# fireguard_v1.net
KiCad netlist of a schematic drawn in EasyEDA
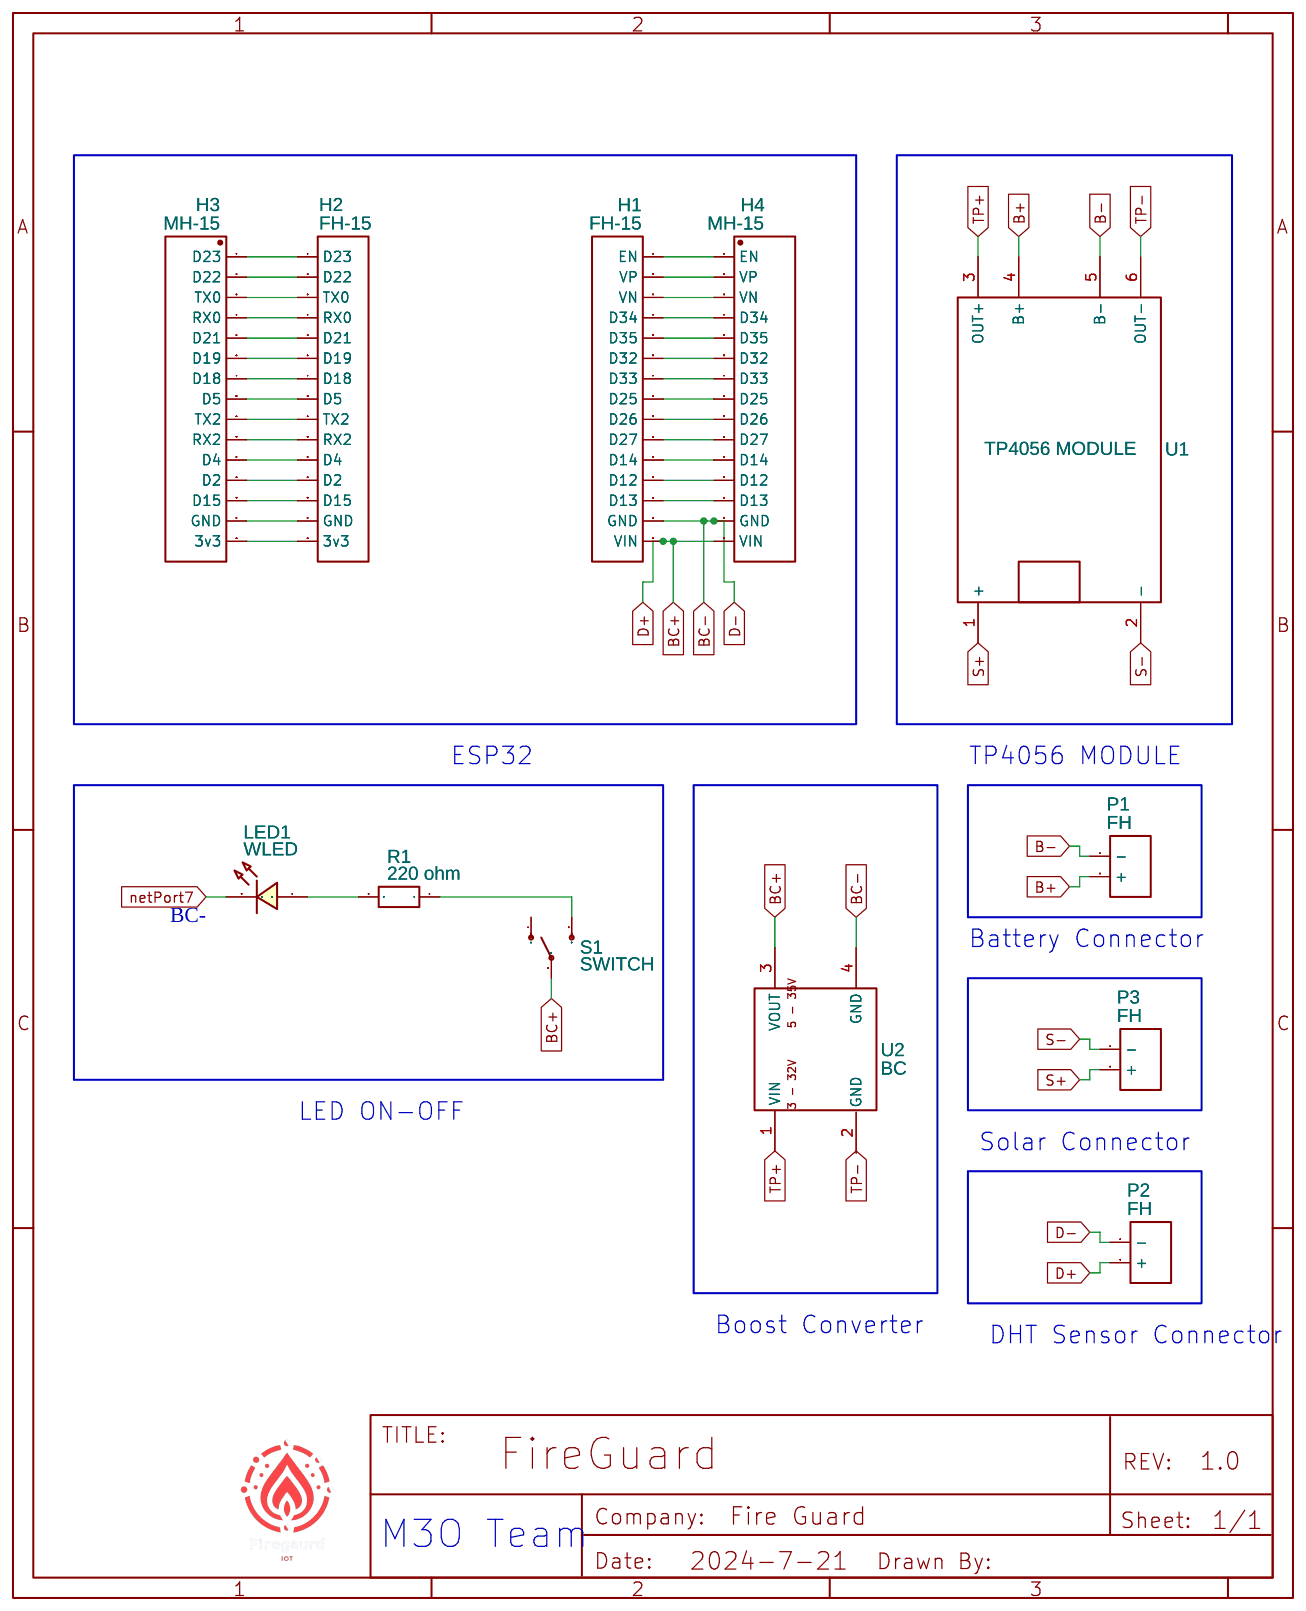
[diagram p0: schematic sheet]

(export (version "E")
  (design (tool "Eeschema 10.0.6"))
  (components
    (comp (ref "H1")
      (value "FH-15")
      (fields (field (name "Manufacturer Part") "B-2200S15P-A120") (field (name "Manufacturer") "Ckmtw(灿科盟)"))
      (libsource (lib "") (part "Header-Female-2.54_1x15_1"))
    )
    (comp (ref "H2")
      (value "FH-15")
      (fields (field (name "Manufacturer Part") "B-2200S15P-A120") (field (name "Manufacturer") "Ckmtw(灿科盟)"))
      (libsource (lib "") (part "Header-Female-2.54_1x15"))
    )
    (comp (ref "H3")
      (value "MH-15")
      (fields (field (name "Manufacturer Part") "B-2100S15P-A110") (field (name "Manufacturer") "Ckmtw(灿科盟)"))
      (libsource (lib "") (part "Header-Male-2.54_1x15_1"))
    )
    (comp (ref "H4")
      (value "MH-15")
      (fields (field (name "Manufacturer Part") "B-2100S15P-A110") (field (name "Manufacturer") "Ckmtw(灿科盟)"))
      (libsource (lib "") (part "Header-Male-2.54_1x15"))
    )
    (comp (ref "LED1") (value "WLED") (libsource (lib "") (part "LED-TH-5mm_B")))
    (comp (ref "P1")
      (value "FH")
      (fields (field (name "Manufacturer Part") "2.54-1*2P母") (field (name "Manufacturer") "BOOMELE(博穆精密)"))
      (libsource (lib "") (part "Header-Female-2.54_1x2"))
    )
    (comp (ref "P2")
      (value "FH")
      (fields (field (name "Manufacturer Part") "2.54-1*2P母") (field (name "Manufacturer") "BOOMELE(博穆精密)"))
      (libsource (lib "") (part "Header-Female-2.54_1x2"))
    )
    (comp (ref "P3")
      (value "FH")
      (fields (field (name "Manufacturer Part") "2.54-1*2P母") (field (name "Manufacturer") "BOOMELE(博穆精密)"))
      (libsource (lib "") (part "Header-Female-2.54_1x2"))
    )
    (comp (ref "R1")
      (value "220 ohm")
      (fields
        (field (name "Manufacturer Part") "Resistor_THT:R_Axial_DIN0309_L9.0mm_D3.2mm_P2.54mm_Vertical")
      )
      (libsource (lib "") (part "RESISTOR_THT{colon}R_AXIAL_DIN0309_L9.0MM_D3.2MM_P2.54MM_VERTICAL"))
    )
    (comp (ref "S1") (value "SWITCH") (libsource (lib "") (part "SWITCH-SPDT-8.5mm")))
    (comp (ref "U1") (value "TP4056 MODULE") (libsource (lib "") (part "TP4056 MODULE")))
    (comp (ref "U2") (value "BC") (libsource (lib "") (part "STEP-UP XL6009E1")))
  )
  (nets
    (net (code "1") (name "B+") (class "Default")
      (node (ref "P1") (pin "2") (pinfunction "+_2") (pintype "input"))
      (node (ref "U1") (pin "4") (pinfunction "B+_4") (pintype "unspecified"))
    )
    (net (code "2") (name "B-") (class "Default")
      (node (ref "P1") (pin "1") (pinfunction "-_1") (pintype "input"))
      (node (ref "U1") (pin "5") (pinfunction "B-_5") (pintype "unspecified"))
    )
    (net (code "3") (name "BC+") (class "Default")
      (node (ref "H1") (pin "15") (pinfunction "VIN_15") (pintype "unspecified"))
      (node (ref "H4") (pin "15") (pinfunction "VIN_15") (pintype "unspecified"))
      (node (ref "P2") (pin "2") (pinfunction "+_2") (pintype "input"))
      (node (ref "S1") (pin "2") (pinfunction "P_2") (pintype "unspecified"))
      (node (ref "U2") (pin "3") (pinfunction "VOUT_3") (pintype "output"))
    )
    (net (code "4") (name "BC-") (class "Default")
      (node (ref "H1") (pin "14") (pinfunction "GND_14") (pintype "unspecified"))
      (node (ref "H4") (pin "14") (pinfunction "GND_14") (pintype "unspecified"))
      (node (ref "P2") (pin "1") (pinfunction "-_1") (pintype "input"))
      (node (ref "U2") (pin "4") (pinfunction "GND_4") (pintype "output"))
    )
    (net (code "5") (name "Net-(H1-D12)") (class "Default")
      (node (ref "H1") (pin "12") (pinfunction "D12_12") (pintype "unspecified"))
      (node (ref "H4") (pin "12") (pinfunction "D12_12") (pintype "unspecified"))
    )
    (net (code "6") (name "Net-(H1-D13)") (class "Default")
      (node (ref "H1") (pin "13") (pinfunction "D13_13") (pintype "unspecified"))
      (node (ref "H4") (pin "13") (pinfunction "D13_13") (pintype "unspecified"))
    )
    (net (code "7") (name "Net-(H1-D14)") (class "Default")
      (node (ref "H1") (pin "11") (pinfunction "D14_11") (pintype "unspecified"))
      (node (ref "H4") (pin "11") (pinfunction "D14_11") (pintype "unspecified"))
    )
    (net (code "8") (name "Net-(H1-D25)") (class "Default")
      (node (ref "H1") (pin "8") (pinfunction "D25_8") (pintype "unspecified"))
      (node (ref "H4") (pin "8") (pinfunction "D25_8") (pintype "unspecified"))
    )
    (net (code "9") (name "Net-(H1-D26)") (class "Default")
      (node (ref "H1") (pin "9") (pinfunction "D26_9") (pintype "unspecified"))
      (node (ref "H4") (pin "9") (pinfunction "D26_9") (pintype "unspecified"))
    )
    (net (code "10") (name "Net-(H1-D27)") (class "Default")
      (node (ref "H1") (pin "10") (pinfunction "D27_10") (pintype "unspecified"))
      (node (ref "H4") (pin "10") (pinfunction "D27_10") (pintype "unspecified"))
    )
    (net (code "11") (name "Net-(H1-D32)") (class "Default")
      (node (ref "H1") (pin "6") (pinfunction "D32_6") (pintype "unspecified"))
      (node (ref "H4") (pin "6") (pinfunction "D32_6") (pintype "unspecified"))
    )
    (net (code "12") (name "Net-(H1-D33)") (class "Default")
      (node (ref "H1") (pin "7") (pinfunction "D33_7") (pintype "unspecified"))
      (node (ref "H4") (pin "7") (pinfunction "D33_7") (pintype "unspecified"))
    )
    (net (code "13") (name "Net-(H1-D34)") (class "Default")
      (node (ref "H1") (pin "4") (pinfunction "D34_4") (pintype "unspecified"))
      (node (ref "H4") (pin "4") (pinfunction "D34_4") (pintype "unspecified"))
    )
    (net (code "14") (name "Net-(H1-D35)") (class "Default")
      (node (ref "H1") (pin "5") (pinfunction "D35_5") (pintype "unspecified"))
      (node (ref "H4") (pin "5") (pinfunction "D35_5") (pintype "unspecified"))
    )
    (net (code "15") (name "Net-(H1-EN)") (class "Default")
      (node (ref "H1") (pin "1") (pinfunction "EN_1") (pintype "unspecified"))
      (node (ref "H4") (pin "1") (pinfunction "EN_1") (pintype "unspecified"))
    )
    (net (code "16") (name "Net-(H1-VN)") (class "Default")
      (node (ref "H1") (pin "3") (pinfunction "VN_3") (pintype "unspecified"))
      (node (ref "H4") (pin "3") (pinfunction "VN_3") (pintype "unspecified"))
    )
    (net (code "17") (name "Net-(H1-VP)") (class "Default")
      (node (ref "H1") (pin "2") (pinfunction "VP_2") (pintype "unspecified"))
      (node (ref "H4") (pin "2") (pinfunction "VP_2") (pintype "unspecified"))
    )
    (net (code "18") (name "Net-(H2-3v3)") (class "Default")
      (node (ref "H2") (pin "15") (pinfunction "3v3_15") (pintype "unspecified"))
      (node (ref "H3") (pin "15") (pinfunction "3v3_15") (pintype "unspecified"))
    )
    (net (code "19") (name "Net-(H2-D2)") (class "Default")
      (node (ref "H2") (pin "12") (pinfunction "D2_12") (pintype "unspecified"))
      (node (ref "H3") (pin "12") (pinfunction "D2_12") (pintype "unspecified"))
    )
    (net (code "20") (name "Net-(H2-D4)") (class "Default")
      (node (ref "H2") (pin "11") (pinfunction "D4_11") (pintype "unspecified"))
      (node (ref "H3") (pin "11") (pinfunction "D4_11") (pintype "unspecified"))
    )
    (net (code "21") (name "Net-(H2-D5)") (class "Default")
      (node (ref "H2") (pin "8") (pinfunction "D5_8") (pintype "unspecified"))
      (node (ref "H3") (pin "8") (pinfunction "D5_8") (pintype "unspecified"))
    )
    (net (code "22") (name "Net-(H2-D15)") (class "Default")
      (node (ref "H2") (pin "13") (pinfunction "D15_13") (pintype "unspecified"))
      (node (ref "H3") (pin "13") (pinfunction "D15_13") (pintype "unspecified"))
    )
    (net (code "23") (name "Net-(H2-D18)") (class "Default")
      (node (ref "H2") (pin "7") (pinfunction "D18_7") (pintype "unspecified"))
      (node (ref "H3") (pin "7") (pinfunction "D18_7") (pintype "unspecified"))
    )
    (net (code "24") (name "Net-(H2-D19)") (class "Default")
      (node (ref "H2") (pin "6") (pinfunction "D19_6") (pintype "unspecified"))
      (node (ref "H3") (pin "6") (pinfunction "D19_6") (pintype "unspecified"))
    )
    (net (code "25") (name "Net-(H2-D21)") (class "Default")
      (node (ref "H2") (pin "5") (pinfunction "D21_5") (pintype "unspecified"))
      (node (ref "H3") (pin "5") (pinfunction "D21_5") (pintype "unspecified"))
    )
    (net (code "26") (name "Net-(H2-D22)") (class "Default")
      (node (ref "H2") (pin "2") (pinfunction "D22_2") (pintype "unspecified"))
      (node (ref "H3") (pin "2") (pinfunction "D22_2") (pintype "unspecified"))
    )
    (net (code "27") (name "Net-(H2-D23)") (class "Default")
      (node (ref "H2") (pin "1") (pinfunction "D23_1") (pintype "unspecified"))
      (node (ref "H3") (pin "1") (pinfunction "D23_1") (pintype "unspecified"))
    )
    (net (code "28") (name "Net-(H2-GND)") (class "Default")
      (node (ref "H2") (pin "14") (pinfunction "GND_14") (pintype "unspecified"))
      (node (ref "H3") (pin "14") (pinfunction "GND_14") (pintype "unspecified"))
    )
    (net (code "29") (name "Net-(H2-RX0)") (class "Default")
      (node (ref "H2") (pin "4") (pinfunction "RX0_4") (pintype "unspecified"))
      (node (ref "H3") (pin "4") (pinfunction "RX0_4") (pintype "unspecified"))
    )
    (net (code "30") (name "Net-(H2-RX2)") (class "Default")
      (node (ref "H2") (pin "10") (pinfunction "RX2_10") (pintype "unspecified"))
      (node (ref "H3") (pin "10") (pinfunction "RX2_10") (pintype "unspecified"))
    )
    (net (code "31") (name "Net-(H2-TX0)") (class "Default")
      (node (ref "H2") (pin "3") (pinfunction "TX0_3") (pintype "unspecified"))
      (node (ref "H3") (pin "3") (pinfunction "TX0_3") (pintype "unspecified"))
    )
    (net (code "32") (name "Net-(H2-TX2)") (class "Default")
      (node (ref "H2") (pin "9") (pinfunction "TX2_9") (pintype "unspecified"))
      (node (ref "H3") (pin "9") (pinfunction "TX2_9") (pintype "unspecified"))
    )
    (net (code "33") (name "Net-(LED1-Pad1)") (class "Default")
      (node (ref "LED1") (pin "1") (pinfunction "1_1") (pintype "unspecified"))
      (node (ref "R1") (pin "2") (pinfunction "2_2") (pintype "unspecified"))
    )
    (net (code "34") (name "Net-(S1-S)") (class "Default")
      (node (ref "R1") (pin "1") (pinfunction "1_1") (pintype "unspecified"))
      (node (ref "S1") (pin "3") (pinfunction "S_3") (pintype "unspecified"))
    )
    (net (code "35") (name "S+") (class "Default")
      (node (ref "P3") (pin "2") (pinfunction "+_2") (pintype "input"))
      (node (ref "U1") (pin "1") (pinfunction "+_1") (pintype "unspecified"))
    )
    (net (code "36") (name "S-") (class "Default")
      (node (ref "P3") (pin "1") (pinfunction "-_1") (pintype "input"))
      (node (ref "U1") (pin "2") (pinfunction "-_2") (pintype "unspecified"))
    )
    (net (code "37") (name "TP+") (class "Default")
      (node (ref "U1") (pin "3") (pinfunction "OUT+_3") (pintype "unspecified"))
      (node (ref "U2") (pin "1") (pinfunction "VIN_1") (pintype "passive"))
    )
    (net (code "38") (name "TP-") (class "Default")
      (node (ref "U1") (pin "6") (pinfunction "OUT-_6") (pintype "unspecified"))
      (node (ref "U2") (pin "2") (pinfunction "GND_2") (pintype "passive"))
    )
    (net (code "39") (name "netPort7") (class "Default")
      (node (ref "LED1") (pin "2") (pinfunction "2_2") (pintype "unspecified"))
    )
    (net (code "40") (name "unconnected-(S1-O-Pad1)") (class "Default")
      (node (ref "S1") (pin "1") (pinfunction "O_1") (pintype "unspecified"))
    )
  )
)
